# simple_sequencer.net
KiCad netlist of a schematic drawn in EAGLE
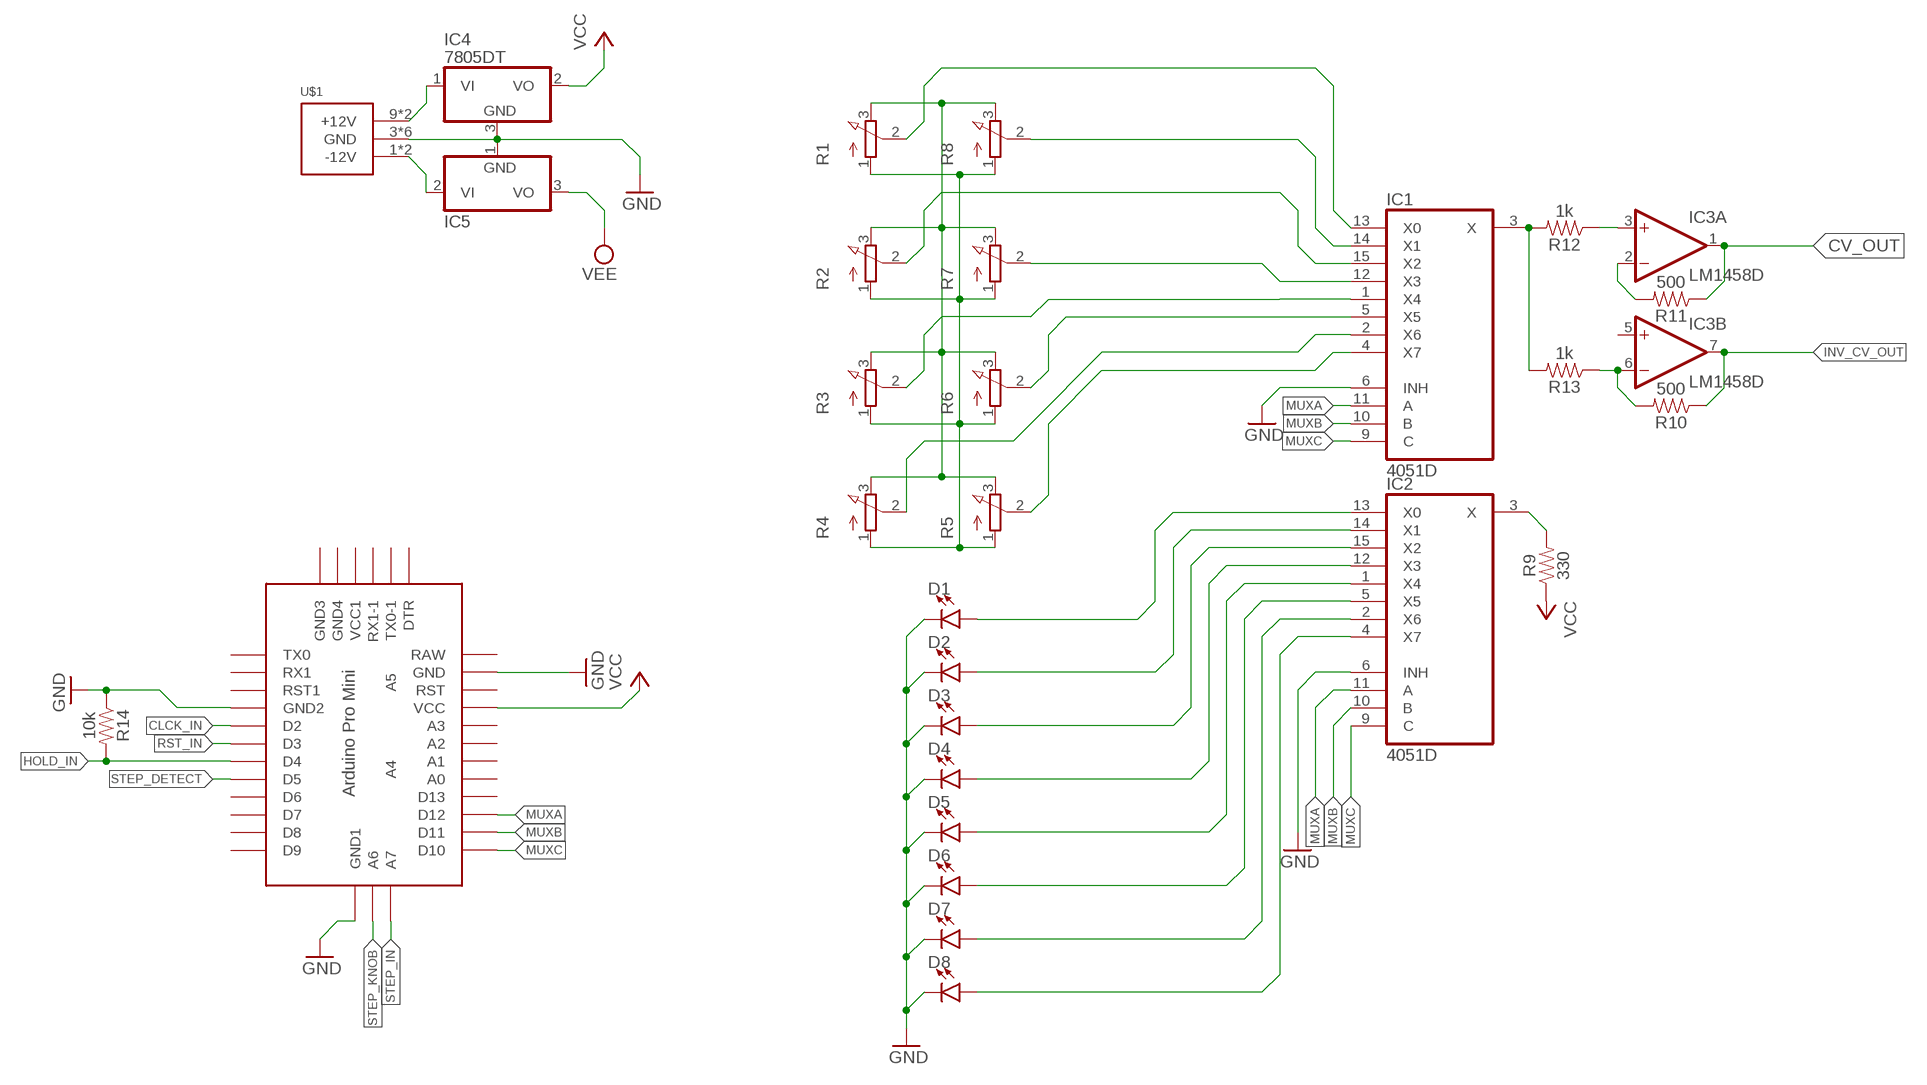
[diagram p0: schematic, sheet 1]

(export (version "E")
  (design (tool "Eeschema 10.0.6"))
  (components
    (comp (ref "D1")
      (value "LED5MM")
      (footprint "eagle-import:LED_5MM")
      (libsource (lib "eagle-import") (part "LED5MM"))
    )
    (comp (ref "D2")
      (value "LED5MM")
      (footprint "eagle-import:LED_5MM")
      (libsource (lib "eagle-import") (part "LED5MM"))
    )
    (comp (ref "D3")
      (value "LED5MM")
      (footprint "eagle-import:LED_5MM")
      (libsource (lib "eagle-import") (part "LED5MM"))
    )
    (comp (ref "D4")
      (value "LED5MM")
      (footprint "eagle-import:LED_5MM")
      (libsource (lib "eagle-import") (part "LED5MM"))
    )
    (comp (ref "D5")
      (value "LED5MM")
      (footprint "eagle-import:LED_5MM")
      (libsource (lib "eagle-import") (part "LED5MM"))
    )
    (comp (ref "D6")
      (value "LED5MM")
      (footprint "eagle-import:LED_5MM")
      (libsource (lib "eagle-import") (part "LED5MM"))
    )
    (comp (ref "D7")
      (value "LED5MM")
      (footprint "eagle-import:LED_5MM")
      (libsource (lib "eagle-import") (part "LED5MM"))
    )
    (comp (ref "D8")
      (value "LED5MM")
      (footprint "eagle-import:LED_5MM")
      (libsource (lib "eagle-import") (part "LED5MM"))
    )
    (comp (ref "IC1")
      (value "4051D")
      (footprint "eagle-import:SO16")
      (libsource (lib "eagle-import") (part "4051D"))
    )
    (comp (ref "IC2")
      (value "4051D")
      (footprint "eagle-import:SO16")
      (libsource (lib "eagle-import") (part "4051D"))
    )
    (comp (ref "IC3")
      (value "LM1458D")
      (footprint "eagle-import:SO08")
      (libsource (lib "eagle-import") (part "1458DLM"))
    )
    (comp (ref "IC4")
      (value "7805DT")
      (footprint "eagle-import:TO252")
      (libsource (lib "eagle-import") (part "78DT05"))
    )
    (comp (ref "IC5")
      (value "7905T")
      (footprint "eagle-import:TO220H")
      (libsource (lib "eagle-import") (part "79T05"))
    )
    (comp (ref "R1")
      (value "3RP/1610N")
      (footprint "eagle-import:3RP_1610N")
      (libsource (lib "eagle-import") (part "3RP/1610N"))
    )
    (comp (ref "R2")
      (value "3RP/1610N")
      (footprint "eagle-import:3RP_1610N")
      (libsource (lib "eagle-import") (part "3RP/1610N"))
    )
    (comp (ref "R3")
      (value "3RP/1610N")
      (footprint "eagle-import:3RP_1610N")
      (libsource (lib "eagle-import") (part "3RP/1610N"))
    )
    (comp (ref "R4")
      (value "3RP/1610N")
      (footprint "eagle-import:3RP_1610N")
      (libsource (lib "eagle-import") (part "3RP/1610N"))
    )
    (comp (ref "R5")
      (value "3RP/1610N")
      (footprint "eagle-import:3RP_1610N")
      (libsource (lib "eagle-import") (part "3RP/1610N"))
    )
    (comp (ref "R6")
      (value "3RP/1610N")
      (footprint "eagle-import:3RP_1610N")
      (libsource (lib "eagle-import") (part "3RP/1610N"))
    )
    (comp (ref "R7")
      (value "3RP/1610N")
      (footprint "eagle-import:3RP_1610N")
      (libsource (lib "eagle-import") (part "3RP/1610N"))
    )
    (comp (ref "R8")
      (value "3RP/1610N")
      (footprint "eagle-import:3RP_1610N")
      (libsource (lib "eagle-import") (part "3RP/1610N"))
    )
    (comp (ref "R9")
      (value "330")
      (footprint "eagle-import:AXIAL-0.3")
      (libsource (lib "eagle-import") (part "330OHM-HORIZ-1/10W-5%"))
    )
    (comp (ref "R10")
      (value "500")
      (footprint "eagle-import:AXIAL-0.3")
      (libsource (lib "eagle-import") (part "330OHM-HORIZ-1/10W-5%"))
    )
    (comp (ref "R11")
      (value "500")
      (footprint "eagle-import:AXIAL-0.3")
      (libsource (lib "eagle-import") (part "330OHM-HORIZ-1/10W-5%"))
    )
    (comp (ref "R12")
      (value "1k")
      (footprint "eagle-import:AXIAL-0.3")
      (libsource (lib "eagle-import") (part "330OHM-HORIZ-1/10W-5%"))
    )
    (comp (ref "R13")
      (value "1k")
      (footprint "eagle-import:AXIAL-0.3")
      (libsource (lib "eagle-import") (part "330OHM-HORIZ-1/10W-5%"))
    )
    (comp (ref "R14")
      (value "10k")
      (footprint "eagle-import:AXIAL-0.3")
      (libsource (lib "eagle-import") (part "330OHM-HORIZ-1/10W-5%"))
    )
    (comp (ref "U$1")
      (value "POWER_SIMPLE10")
      (footprint "eagle-import:POWER_10")
      (libsource (lib "eagle-import") (part "POWER_SIMPLE10"))
    )
    (comp (ref "U$2")
      (value "ABK-PRO-MINI")
      (footprint "eagle-import:ABK-PRO-MINI")
      (libsource (lib "eagle-import") (part "ABK-PRO-MINI"))
    )
  )
  (nets
    (net (code "1") (name "CLCK_IN") (class "Default")
      (node (ref "U$2") (pin "D2") (pinfunction "D2_D2") (pintype "bidirectional"))
    )
    (net (code "2") (name "CV_OUT") (class "Default")
      (node (ref "IC3") (pin "1") (pinfunction "OUT_1") (pintype "output"))
      (node (ref "R11") (pin "P$1") (pinfunction "1_P$1") (pintype "passive"))
    )
    (net (code "3") (name "GND") (class "Default")
      (node (ref "D1") (pin "K") (pinfunction "C_K") (pintype "passive"))
      (node (ref "D2") (pin "K") (pinfunction "C_K") (pintype "passive"))
      (node (ref "D3") (pin "K") (pinfunction "C_K") (pintype "passive"))
      (node (ref "D4") (pin "K") (pinfunction "C_K") (pintype "passive"))
      (node (ref "D5") (pin "K") (pinfunction "C_K") (pintype "passive"))
      (node (ref "D6") (pin "K") (pinfunction "C_K") (pintype "passive"))
      (node (ref "D7") (pin "K") (pinfunction "C_K") (pintype "passive"))
      (node (ref "D8") (pin "K") (pinfunction "C_K") (pintype "passive"))
      (node (ref "IC1") (pin "6") (pinfunction "INH_6") (pintype "input"))
      (node (ref "IC2") (pin "6") (pinfunction "INH_6") (pintype "input"))
      (node (ref "IC4") (pin "3") (pinfunction "GND_3") (pintype "passive"))
      (node (ref "IC5") (pin "1") (pinfunction "GND_1") (pintype "passive"))
      (node (ref "R14") (pin "P$1") (pinfunction "1_P$1") (pintype "passive"))
      (node (ref "U$1") (pin "3") (pinfunction "GND_3") (pintype "bidirectional"))
      (node (ref "U$1") (pin "4") (pinfunction "GND_4") (pintype "bidirectional"))
      (node (ref "U$1") (pin "5") (pinfunction "GND_5") (pintype "bidirectional"))
      (node (ref "U$1") (pin "6") (pinfunction "GND_6") (pintype "bidirectional"))
      (node (ref "U$1") (pin "7") (pinfunction "GND_7") (pintype "bidirectional"))
      (node (ref "U$1") (pin "8") (pinfunction "GND_8") (pintype "bidirectional"))
      (node (ref "U$2") (pin "GND") (pinfunction "GND_GND") (pintype "bidirectional"))
      (node (ref "U$2") (pin "GND1") (pinfunction "GND2_GND1") (pintype "bidirectional"))
      (node (ref "U$2") (pin "GND4") (pinfunction "GND1_GND4") (pintype "bidirectional"))
    )
    (net (code "4") (name "HOLD_IN") (class "Default")
      (node (ref "R14") (pin "P$2") (pinfunction "2_P$2") (pintype "passive"))
      (node (ref "U$2") (pin "D4") (pinfunction "D4_D4") (pintype "bidirectional"))
    )
    (net (code "5") (name "INV_CV_OUT") (class "Default")
      (node (ref "IC3") (pin "7") (pinfunction "OUT_7") (pintype "output"))
      (node (ref "R10") (pin "P$1") (pinfunction "1_P$1") (pintype "passive"))
    )
    (net (code "6") (name "MUXA") (class "Default")
      (node (ref "IC1") (pin "11") (pinfunction "A_11") (pintype "input"))
      (node (ref "IC2") (pin "11") (pinfunction "A_11") (pintype "input"))
      (node (ref "U$2") (pin "D12") (pinfunction "D12_D12") (pintype "bidirectional"))
    )
    (net (code "7") (name "MUXB") (class "Default")
      (node (ref "IC1") (pin "10") (pinfunction "B_10") (pintype "input"))
      (node (ref "IC2") (pin "10") (pinfunction "B_10") (pintype "input"))
      (node (ref "U$2") (pin "D11") (pinfunction "D11_D11") (pintype "bidirectional"))
    )
    (net (code "8") (name "MUXC") (class "Default")
      (node (ref "IC1") (pin "9") (pinfunction "C_9") (pintype "input"))
      (node (ref "IC2") (pin "9") (pinfunction "C_9") (pintype "input"))
      (node (ref "U$2") (pin "D10") (pinfunction "D10_D10") (pintype "bidirectional"))
    )
    (net (code "9") (name "Net-(IC1A-X)") (class "Default")
      (node (ref "IC1") (pin "3") (pinfunction "X_3") (pintype "bidirectional"))
      (node (ref "R12") (pin "P$2") (pinfunction "2_P$2") (pintype "passive"))
      (node (ref "R13") (pin "P$2") (pinfunction "2_P$2") (pintype "passive"))
    )
    (net (code "10") (name "Net-(IC1A-X0)") (class "Default")
      (node (ref "IC1") (pin "13") (pinfunction "X0_13") (pintype "bidirectional"))
      (node (ref "R1") (pin "2") (pinfunction "S_2") (pintype "passive"))
    )
    (net (code "11") (name "Net-(IC1A-X1)") (class "Default")
      (node (ref "IC1") (pin "14") (pinfunction "X1_14") (pintype "bidirectional"))
      (node (ref "R8") (pin "2") (pinfunction "S_2") (pintype "passive"))
    )
    (net (code "12") (name "Net-(IC1A-X2)") (class "Default")
      (node (ref "IC1") (pin "15") (pinfunction "X2_15") (pintype "bidirectional"))
      (node (ref "R2") (pin "2") (pinfunction "S_2") (pintype "passive"))
    )
    (net (code "13") (name "Net-(IC1A-X3)") (class "Default")
      (node (ref "IC1") (pin "12") (pinfunction "X3_12") (pintype "bidirectional"))
      (node (ref "R7") (pin "2") (pinfunction "S_2") (pintype "passive"))
    )
    (net (code "14") (name "Net-(IC1A-X4)") (class "Default")
      (node (ref "IC1") (pin "1") (pinfunction "X4_1") (pintype "bidirectional"))
      (node (ref "R3") (pin "2") (pinfunction "S_2") (pintype "passive"))
    )
    (net (code "15") (name "Net-(IC1A-X5)") (class "Default")
      (node (ref "IC1") (pin "5") (pinfunction "X5_5") (pintype "bidirectional"))
      (node (ref "R6") (pin "2") (pinfunction "S_2") (pintype "passive"))
    )
    (net (code "16") (name "Net-(IC1A-X6)") (class "Default")
      (node (ref "IC1") (pin "2") (pinfunction "X6_2") (pintype "bidirectional"))
      (node (ref "R4") (pin "2") (pinfunction "S_2") (pintype "passive"))
    )
    (net (code "17") (name "Net-(IC1A-X7)") (class "Default")
      (node (ref "IC1") (pin "4") (pinfunction "X7_4") (pintype "bidirectional"))
      (node (ref "R5") (pin "2") (pinfunction "S_2") (pintype "passive"))
    )
    (net (code "18") (name "Net-(IC2A-X)") (class "Default")
      (node (ref "IC2") (pin "3") (pinfunction "X_3") (pintype "bidirectional"))
      (node (ref "R9") (pin "P$2") (pinfunction "2_P$2") (pintype "passive"))
    )
    (net (code "19") (name "Net-(IC2A-X0)") (class "Default")
      (node (ref "D1") (pin "A") (pinfunction "A_A") (pintype "passive"))
      (node (ref "IC2") (pin "13") (pinfunction "X0_13") (pintype "bidirectional"))
    )
    (net (code "20") (name "Net-(IC2A-X1)") (class "Default")
      (node (ref "D2") (pin "A") (pinfunction "A_A") (pintype "passive"))
      (node (ref "IC2") (pin "14") (pinfunction "X1_14") (pintype "bidirectional"))
    )
    (net (code "21") (name "Net-(IC2A-X2)") (class "Default")
      (node (ref "D3") (pin "A") (pinfunction "A_A") (pintype "passive"))
      (node (ref "IC2") (pin "15") (pinfunction "X2_15") (pintype "bidirectional"))
    )
    (net (code "22") (name "Net-(IC2A-X3)") (class "Default")
      (node (ref "D4") (pin "A") (pinfunction "A_A") (pintype "passive"))
      (node (ref "IC2") (pin "12") (pinfunction "X3_12") (pintype "bidirectional"))
    )
    (net (code "23") (name "Net-(IC2A-X4)") (class "Default")
      (node (ref "D5") (pin "A") (pinfunction "A_A") (pintype "passive"))
      (node (ref "IC2") (pin "1") (pinfunction "X4_1") (pintype "bidirectional"))
    )
    (net (code "24") (name "Net-(IC2A-X5)") (class "Default")
      (node (ref "D6") (pin "A") (pinfunction "A_A") (pintype "passive"))
      (node (ref "IC2") (pin "5") (pinfunction "X5_5") (pintype "bidirectional"))
    )
    (net (code "25") (name "Net-(IC2A-X6)") (class "Default")
      (node (ref "D7") (pin "A") (pinfunction "A_A") (pintype "passive"))
      (node (ref "IC2") (pin "2") (pinfunction "X6_2") (pintype "bidirectional"))
    )
    (net (code "26") (name "Net-(IC2A-X7)") (class "Default")
      (node (ref "D8") (pin "A") (pinfunction "A_A") (pintype "passive"))
      (node (ref "IC2") (pin "4") (pinfunction "X7_4") (pintype "bidirectional"))
    )
    (net (code "27") (name "Net-(IC3A-+IN)") (class "Default")
      (node (ref "IC3") (pin "3") (pinfunction "+IN_3") (pintype "input"))
      (node (ref "R12") (pin "P$1") (pinfunction "1_P$1") (pintype "passive"))
    )
    (net (code "28") (name "Net-(IC3A--IN)") (class "Default")
      (node (ref "IC3") (pin "2") (pinfunction "-IN_2") (pintype "input"))
      (node (ref "R11") (pin "P$2") (pinfunction "2_P$2") (pintype "passive"))
    )
    (net (code "29") (name "Net-(IC3B--IN)") (class "Default")
      (node (ref "IC3") (pin "6") (pinfunction "-IN_6") (pintype "input"))
      (node (ref "R10") (pin "P$2") (pinfunction "2_P$2") (pintype "passive"))
      (node (ref "R13") (pin "P$1") (pinfunction "1_P$1") (pintype "passive"))
    )
    (net (code "30") (name "Net-(IC4-VI)") (class "Default")
      (node (ref "IC4") (pin "1") (pinfunction "VI_1") (pintype "input"))
      (node (ref "U$1") (pin "10") (pinfunction "+12V_10") (pintype "bidirectional"))
      (node (ref "U$1") (pin "9") (pinfunction "+12V_9") (pintype "bidirectional"))
    )
    (net (code "31") (name "Net-(IC5-VI)") (class "Default")
      (node (ref "IC5") (pin "2") (pinfunction "VI_2") (pintype "input"))
      (node (ref "U$1") (pin "1") (pinfunction "-12V_1") (pintype "bidirectional"))
      (node (ref "U$1") (pin "2") (pinfunction "-12V_2") (pintype "bidirectional"))
    )
    (net (code "32") (name "Net-(R1-A)") (class "Default")
      (node (ref "R1") (pin "1") (pinfunction "A_1") (pintype "passive"))
      (node (ref "R2") (pin "1") (pinfunction "A_1") (pintype "passive"))
      (node (ref "R3") (pin "1") (pinfunction "A_1") (pintype "passive"))
      (node (ref "R4") (pin "1") (pinfunction "A_1") (pintype "passive"))
      (node (ref "R5") (pin "1") (pinfunction "A_1") (pintype "passive"))
      (node (ref "R6") (pin "1") (pinfunction "A_1") (pintype "passive"))
      (node (ref "R7") (pin "1") (pinfunction "A_1") (pintype "passive"))
      (node (ref "R8") (pin "1") (pinfunction "A_1") (pintype "passive"))
    )
    (net (code "33") (name "Net-(R1-E)") (class "Default")
      (node (ref "R1") (pin "3") (pinfunction "E_3") (pintype "passive"))
      (node (ref "R2") (pin "3") (pinfunction "E_3") (pintype "passive"))
      (node (ref "R3") (pin "3") (pinfunction "E_3") (pintype "passive"))
      (node (ref "R4") (pin "3") (pinfunction "E_3") (pintype "passive"))
      (node (ref "R5") (pin "3") (pinfunction "E_3") (pintype "passive"))
      (node (ref "R6") (pin "3") (pinfunction "E_3") (pintype "passive"))
      (node (ref "R7") (pin "3") (pinfunction "E_3") (pintype "passive"))
      (node (ref "R8") (pin "3") (pinfunction "E_3") (pintype "passive"))
    )
    (net (code "34") (name "RST_IN") (class "Default")
      (node (ref "U$2") (pin "D3") (pinfunction "D3_D3") (pintype "bidirectional"))
    )
    (net (code "35") (name "STEP_DETECT") (class "Default")
      (node (ref "U$2") (pin "D5") (pinfunction "D5_D5") (pintype "bidirectional"))
    )
    (net (code "36") (name "STEP_IN") (class "Default")
      (node (ref "U$2") (pin "A7") (pinfunction "A7_A7") (pintype "bidirectional"))
    )
    (net (code "37") (name "STEP_KNOB") (class "Default")
      (node (ref "U$2") (pin "A6") (pinfunction "A6_A6") (pintype "bidirectional"))
    )
    (net (code "38") (name "VCC") (class "Default")
      (node (ref "IC4") (pin "2") (pinfunction "VO_2") (pintype "passive"))
      (node (ref "R9") (pin "P$1") (pinfunction "1_P$1") (pintype "passive"))
      (node (ref "U$2") (pin "VCC") (pinfunction "VCC_VCC") (pintype "bidirectional"))
    )
    (net (code "39") (name "VEE") (class "Default")
      (node (ref "IC5") (pin "3") (pinfunction "VO_3") (pintype "passive"))
    )
    (net (code "40") (name "unconnected-(IC3B-+IN-Pad5)") (class "Default")
      (node (ref "IC3") (pin "5") (pinfunction "+IN_5") (pintype "input"))
    )
    (net (code "41") (name "unconnected-(U$2-GND3-PadGND2)") (class "Default")
      (node (ref "U$2") (pin "GND2") (pinfunction "GND3_GND2") (pintype "bidirectional"))
    )
    (net (code "42") (name "unconnected-(U$2-GND4-PadGND3)") (class "Default")
      (node (ref "U$2") (pin "GND3") (pinfunction "GND4_GND3") (pintype "bidirectional"))
    )
    (net (code "43") (name "unconnected-(U$2-PadA0)") (class "Default")
      (node (ref "U$2") (pin "A0") (pinfunction "A0_A0") (pintype "bidirectional"))
    )
    (net (code "44") (name "unconnected-(U$2-PadA1)") (class "Default")
      (node (ref "U$2") (pin "A1") (pinfunction "A1_A1") (pintype "bidirectional"))
    )
    (net (code "45") (name "unconnected-(U$2-PadA2)") (class "Default")
      (node (ref "U$2") (pin "A2") (pinfunction "A2_A2") (pintype "bidirectional"))
    )
    (net (code "46") (name "unconnected-(U$2-PadA3)") (class "Default")
      (node (ref "U$2") (pin "A3") (pinfunction "A3_A3") (pintype "bidirectional"))
    )
    (net (code "47") (name "unconnected-(U$2-PadA4)") (class "Default")
      (node (ref "U$2") (pin "A4") (pinfunction "A4_A4") (pintype "bidirectional"))
    )
    (net (code "48") (name "unconnected-(U$2-PadA5)") (class "Default")
      (node (ref "U$2") (pin "A5") (pinfunction "A5_A5") (pintype "bidirectional"))
    )
    (net (code "49") (name "unconnected-(U$2-PadD6)") (class "Default")
      (node (ref "U$2") (pin "D6") (pinfunction "D6_D6") (pintype "bidirectional"))
    )
    (net (code "50") (name "unconnected-(U$2-PadD7)") (class "Default")
      (node (ref "U$2") (pin "D7") (pinfunction "D7_D7") (pintype "bidirectional"))
    )
    (net (code "51") (name "unconnected-(U$2-PadD8)") (class "Default")
      (node (ref "U$2") (pin "D8") (pinfunction "D8_D8") (pintype "bidirectional"))
    )
    (net (code "52") (name "unconnected-(U$2-PadD9)") (class "Default")
      (node (ref "U$2") (pin "D9") (pinfunction "D9_D9") (pintype "bidirectional"))
    )
    (net (code "53") (name "unconnected-(U$2-PadD13)") (class "Default")
      (node (ref "U$2") (pin "D13") (pinfunction "D13_D13") (pintype "bidirectional"))
    )
    (net (code "54") (name "unconnected-(U$2-PadDTR)") (class "Default")
      (node (ref "U$2") (pin "DTR") (pinfunction "DTR_DTR") (pintype "bidirectional"))
    )
    (net (code "55") (name "unconnected-(U$2-PadRAW)") (class "Default")
      (node (ref "U$2") (pin "RAW") (pinfunction "RAW_RAW") (pintype "bidirectional"))
    )
    (net (code "56") (name "unconnected-(U$2-PadRST)") (class "Default")
      (node (ref "U$2") (pin "RST") (pinfunction "RST_RST") (pintype "bidirectional"))
    )
    (net (code "57") (name "unconnected-(U$2-PadRST1)") (class "Default")
      (node (ref "U$2") (pin "RST1") (pinfunction "RST1_RST1") (pintype "bidirectional"))
    )
    (net (code "58") (name "unconnected-(U$2-PadRX1)") (class "Default")
      (node (ref "U$2") (pin "RX1") (pinfunction "RX1_RX1") (pintype "bidirectional"))
    )
    (net (code "59") (name "unconnected-(U$2-PadRX1-1)") (class "Default")
      (node (ref "U$2") (pin "RX1-1") (pinfunction "RX1-1_RX1-1") (pintype "bidirectional"))
    )
    (net (code "60") (name "unconnected-(U$2-PadTX0)") (class "Default")
      (node (ref "U$2") (pin "TX0") (pinfunction "TX0_TX0") (pintype "bidirectional"))
    )
    (net (code "61") (name "unconnected-(U$2-PadTX0-1)") (class "Default")
      (node (ref "U$2") (pin "TX0-1") (pinfunction "TX0-1_TX0-1") (pintype "bidirectional"))
    )
    (net (code "62") (name "unconnected-(U$2-PadVCC1)") (class "Default")
      (node (ref "U$2") (pin "VCC1") (pinfunction "VCC1_VCC1") (pintype "bidirectional"))
    )
  )
)
